# lightfollower.net
KiCad netlist of a schematic drawn in EAGLE
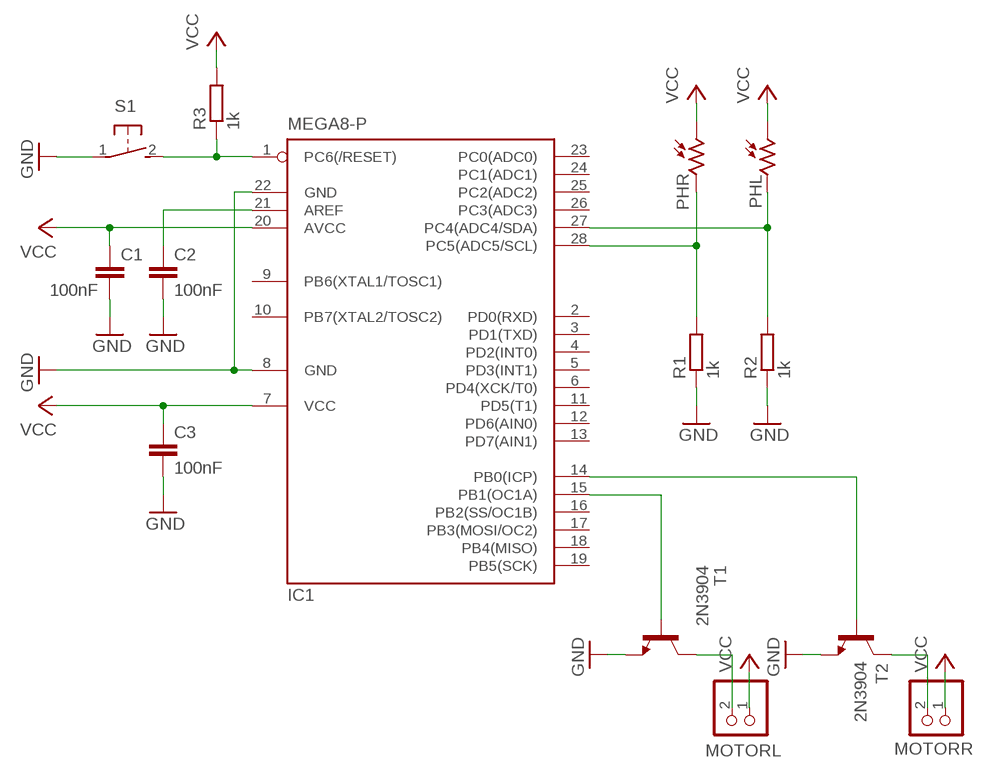
[diagram p0: schematic, sheet 1]

(export (version "E")
  (design (tool "Eeschema 10.0.6"))
  (components
    (comp (ref "C1")
      (value "100nF")
      (footprint "eagle-import:C0805")
      (libsource (lib "eagle-import") (part "C-EUC0805"))
    )
    (comp (ref "C2")
      (value "100nF")
      (footprint "eagle-import:C0805")
      (libsource (lib "eagle-import") (part "C-EUC0805"))
    )
    (comp (ref "C3")
      (value "100nF")
      (footprint "eagle-import:C0805")
      (libsource (lib "eagle-import") (part "C-EUC0805"))
    )
    (comp (ref "IC1")
      (value "MEGA8-P")
      (footprint "eagle-import:DIL28-3")
      (libsource (lib "eagle-import") (part "MEGA8-P"))
    )
    (comp (ref "MOTORL")
      (value "PINHD-1X2")
      (footprint "eagle-import:1X02")
      (libsource (lib "eagle-import") (part "PINHD-1X2"))
    )
    (comp (ref "MOTORR")
      (value "PINHD-1X2")
      (footprint "eagle-import:1X02")
      (libsource (lib "eagle-import") (part "PINHD-1X2"))
    )
    (comp (ref "PHL")
      (value "D1160_12")
      (footprint "eagle-import:D11XX")
      (libsource (lib "eagle-import") (part "D1160_12"))
    )
    (comp (ref "PHR")
      (value "D1160_12")
      (footprint "eagle-import:D11XX")
      (libsource (lib "eagle-import") (part "D1160_12"))
    )
    (comp (ref "R1")
      (value "1k")
      (footprint "eagle-import:0204_5")
      (libsource (lib "eagle-import") (part "R-EU_0204/5"))
    )
    (comp (ref "R2")
      (value "1k")
      (footprint "eagle-import:0204_5")
      (libsource (lib "eagle-import") (part "R-EU_0204/5"))
    )
    (comp (ref "R3")
      (value "1k")
      (footprint "eagle-import:0204_5")
      (libsource (lib "eagle-import") (part "R-EU_0204/5"))
    )
    (comp (ref "S1")
      (value "DTS-3")
      (footprint "eagle-import:DTS-3")
      (libsource (lib "eagle-import") (part "DTS-3"))
    )
    (comp (ref "T1")
      (value "2N3904")
      (footprint "eagle-import:TO92")
      (libsource (lib "eagle-import") (part "2N3904"))
    )
    (comp (ref "T2")
      (value "2N3904")
      (footprint "eagle-import:TO92")
      (libsource (lib "eagle-import") (part "2N3904"))
    )
  )
  (nets
    (net (code "1") (name "GND") (class "Default")
      (node (ref "C1") (pin "2") (pinfunction "2_2") (pintype "passive"))
      (node (ref "C2") (pin "2") (pinfunction "2_2") (pintype "passive"))
      (node (ref "C3") (pin "2") (pinfunction "2_2") (pintype "passive"))
      (node (ref "IC1") (pin "22") (pinfunction "GND_22") (pintype "power_in"))
      (node (ref "IC1") (pin "8") (pinfunction "GND_8") (pintype "power_in"))
      (node (ref "R1") (pin "1") (pinfunction "1_1") (pintype "passive"))
      (node (ref "R2") (pin "1") (pinfunction "1_1") (pintype "passive"))
      (node (ref "S1") (pin "1") (pinfunction "1_1") (pintype "passive"))
      (node (ref "T1") (pin "3") (pinfunction "E_3") (pintype "passive"))
      (node (ref "T2") (pin "3") (pinfunction "E_3") (pintype "passive"))
    )
    (net (code "2") (name "Net-(IC1-AREF)") (class "Default")
      (node (ref "C2") (pin "1") (pinfunction "1_1") (pintype "passive"))
      (node (ref "IC1") (pin "21") (pinfunction "AREF_21") (pintype "passive"))
    )
    (net (code "3") (name "Net-(IC1-PB0(ICP))") (class "Default")
      (node (ref "IC1") (pin "14") (pinfunction "PB0(ICP)_14") (pintype "bidirectional"))
      (node (ref "T2") (pin "2") (pinfunction "B_2") (pintype "passive"))
    )
    (net (code "4") (name "Net-(IC1-PB1(OC1A))") (class "Default")
      (node (ref "IC1") (pin "15") (pinfunction "PB1(OC1A)_15") (pintype "bidirectional"))
      (node (ref "T1") (pin "2") (pinfunction "B_2") (pintype "passive"))
    )
    (net (code "5") (name "Net-(IC1-PC4(ADC4{slash}SDA))") (class "Default")
      (node (ref "IC1") (pin "27") (pinfunction "PC4(ADC4/SDA)_27") (pintype "bidirectional"))
      (node (ref "PHL") (pin "2") (pinfunction "2_2") (pintype "passive"))
      (node (ref "R2") (pin "2") (pinfunction "2_2") (pintype "passive"))
    )
    (net (code "6") (name "Net-(IC1-PC5(ADC5{slash}SCL))") (class "Default")
      (node (ref "IC1") (pin "28") (pinfunction "PC5(ADC5/SCL)_28") (pintype "bidirectional"))
      (node (ref "PHR") (pin "2") (pinfunction "2_2") (pintype "passive"))
      (node (ref "R1") (pin "2") (pinfunction "2_2") (pintype "passive"))
    )
    (net (code "7") (name "Net-(IC1-PC6({slash}RESET))") (class "Default")
      (node (ref "IC1") (pin "1") (pinfunction "PC6(/RESET)_1") (pintype "bidirectional"))
      (node (ref "R3") (pin "1") (pinfunction "1_1") (pintype "passive"))
      (node (ref "S1") (pin "2") (pinfunction "2_2") (pintype "passive"))
    )
    (net (code "8") (name "Net-(T1-C)") (class "Default")
      (node (ref "MOTORL") (pin "2") (pinfunction "2_2") (pintype "passive"))
      (node (ref "T1") (pin "1") (pinfunction "C_1") (pintype "passive"))
    )
    (net (code "9") (name "Net-(T2-C)") (class "Default")
      (node (ref "MOTORR") (pin "2") (pinfunction "2_2") (pintype "passive"))
      (node (ref "T2") (pin "1") (pinfunction "C_1") (pintype "passive"))
    )
    (net (code "10") (name "VCC") (class "Default")
      (node (ref "C1") (pin "1") (pinfunction "1_1") (pintype "passive"))
      (node (ref "C3") (pin "1") (pinfunction "1_1") (pintype "passive"))
      (node (ref "IC1") (pin "20") (pinfunction "AVCC_20") (pintype "power_in"))
      (node (ref "IC1") (pin "7") (pinfunction "VCC_7") (pintype "power_in"))
      (node (ref "MOTORL") (pin "1") (pinfunction "1_1") (pintype "passive"))
      (node (ref "MOTORR") (pin "1") (pinfunction "1_1") (pintype "passive"))
      (node (ref "PHL") (pin "1") (pinfunction "1_1") (pintype "passive"))
      (node (ref "PHR") (pin "1") (pinfunction "1_1") (pintype "passive"))
      (node (ref "R3") (pin "2") (pinfunction "2_2") (pintype "passive"))
    )
    (net (code "11") (name "unconnected-(IC1-PB2(SS{slash}OC1B)-Pad16)") (class "Default")
      (node (ref "IC1") (pin "16") (pinfunction "PB2(SS/OC1B)_16") (pintype "bidirectional"))
    )
    (net (code "12") (name "unconnected-(IC1-PB3(MOSI{slash}OC2)-Pad17)") (class "Default")
      (node (ref "IC1") (pin "17") (pinfunction "PB3(MOSI/OC2)_17") (pintype "bidirectional"))
    )
    (net (code "13") (name "unconnected-(IC1-PB4(MISO)-Pad18)") (class "Default")
      (node (ref "IC1") (pin "18") (pinfunction "PB4(MISO)_18") (pintype "bidirectional"))
    )
    (net (code "14") (name "unconnected-(IC1-PB5(SCK)-Pad19)") (class "Default")
      (node (ref "IC1") (pin "19") (pinfunction "PB5(SCK)_19") (pintype "bidirectional"))
    )
    (net (code "15") (name "unconnected-(IC1-PB6(XTAL1{slash}TOSC1)-Pad9)") (class "Default")
      (node (ref "IC1") (pin "9") (pinfunction "PB6(XTAL1/TOSC1)_9") (pintype "bidirectional"))
    )
    (net (code "16") (name "unconnected-(IC1-PB7(XTAL2{slash}TOSC2)-Pad10)") (class "Default")
      (node (ref "IC1") (pin "10") (pinfunction "PB7(XTAL2/TOSC2)_10") (pintype "bidirectional"))
    )
    (net (code "17") (name "unconnected-(IC1-PC0(ADC0)-Pad23)") (class "Default")
      (node (ref "IC1") (pin "23") (pinfunction "PC0(ADC0)_23") (pintype "bidirectional"))
    )
    (net (code "18") (name "unconnected-(IC1-PC1(ADC1)-Pad24)") (class "Default")
      (node (ref "IC1") (pin "24") (pinfunction "PC1(ADC1)_24") (pintype "bidirectional"))
    )
    (net (code "19") (name "unconnected-(IC1-PC2(ADC2)-Pad25)") (class "Default")
      (node (ref "IC1") (pin "25") (pinfunction "PC2(ADC2)_25") (pintype "bidirectional"))
    )
    (net (code "20") (name "unconnected-(IC1-PC3(ADC3)-Pad26)") (class "Default")
      (node (ref "IC1") (pin "26") (pinfunction "PC3(ADC3)_26") (pintype "bidirectional"))
    )
    (net (code "21") (name "unconnected-(IC1-PD0(RXD)-Pad2)") (class "Default")
      (node (ref "IC1") (pin "2") (pinfunction "PD0(RXD)_2") (pintype "bidirectional"))
    )
    (net (code "22") (name "unconnected-(IC1-PD1(TXD)-Pad3)") (class "Default")
      (node (ref "IC1") (pin "3") (pinfunction "PD1(TXD)_3") (pintype "bidirectional"))
    )
    (net (code "23") (name "unconnected-(IC1-PD2(INT0)-Pad4)") (class "Default")
      (node (ref "IC1") (pin "4") (pinfunction "PD2(INT0)_4") (pintype "bidirectional"))
    )
    (net (code "24") (name "unconnected-(IC1-PD3(INT1)-Pad5)") (class "Default")
      (node (ref "IC1") (pin "5") (pinfunction "PD3(INT1)_5") (pintype "bidirectional"))
    )
    (net (code "25") (name "unconnected-(IC1-PD4(XCK{slash}T0)-Pad6)") (class "Default")
      (node (ref "IC1") (pin "6") (pinfunction "PD4(XCK/T0)_6") (pintype "bidirectional"))
    )
    (net (code "26") (name "unconnected-(IC1-PD5(T1)-Pad11)") (class "Default")
      (node (ref "IC1") (pin "11") (pinfunction "PD5(T1)_11") (pintype "bidirectional"))
    )
    (net (code "27") (name "unconnected-(IC1-PD6(AIN0)-Pad12)") (class "Default")
      (node (ref "IC1") (pin "12") (pinfunction "PD6(AIN0)_12") (pintype "bidirectional"))
    )
    (net (code "28") (name "unconnected-(IC1-PD7(AIN1)-Pad13)") (class "Default")
      (node (ref "IC1") (pin "13") (pinfunction "PD7(AIN1)_13") (pintype "bidirectional"))
    )
  )
)
